# 914-STM32.net
KiCad netlist of a schematic drawn in EAGLE
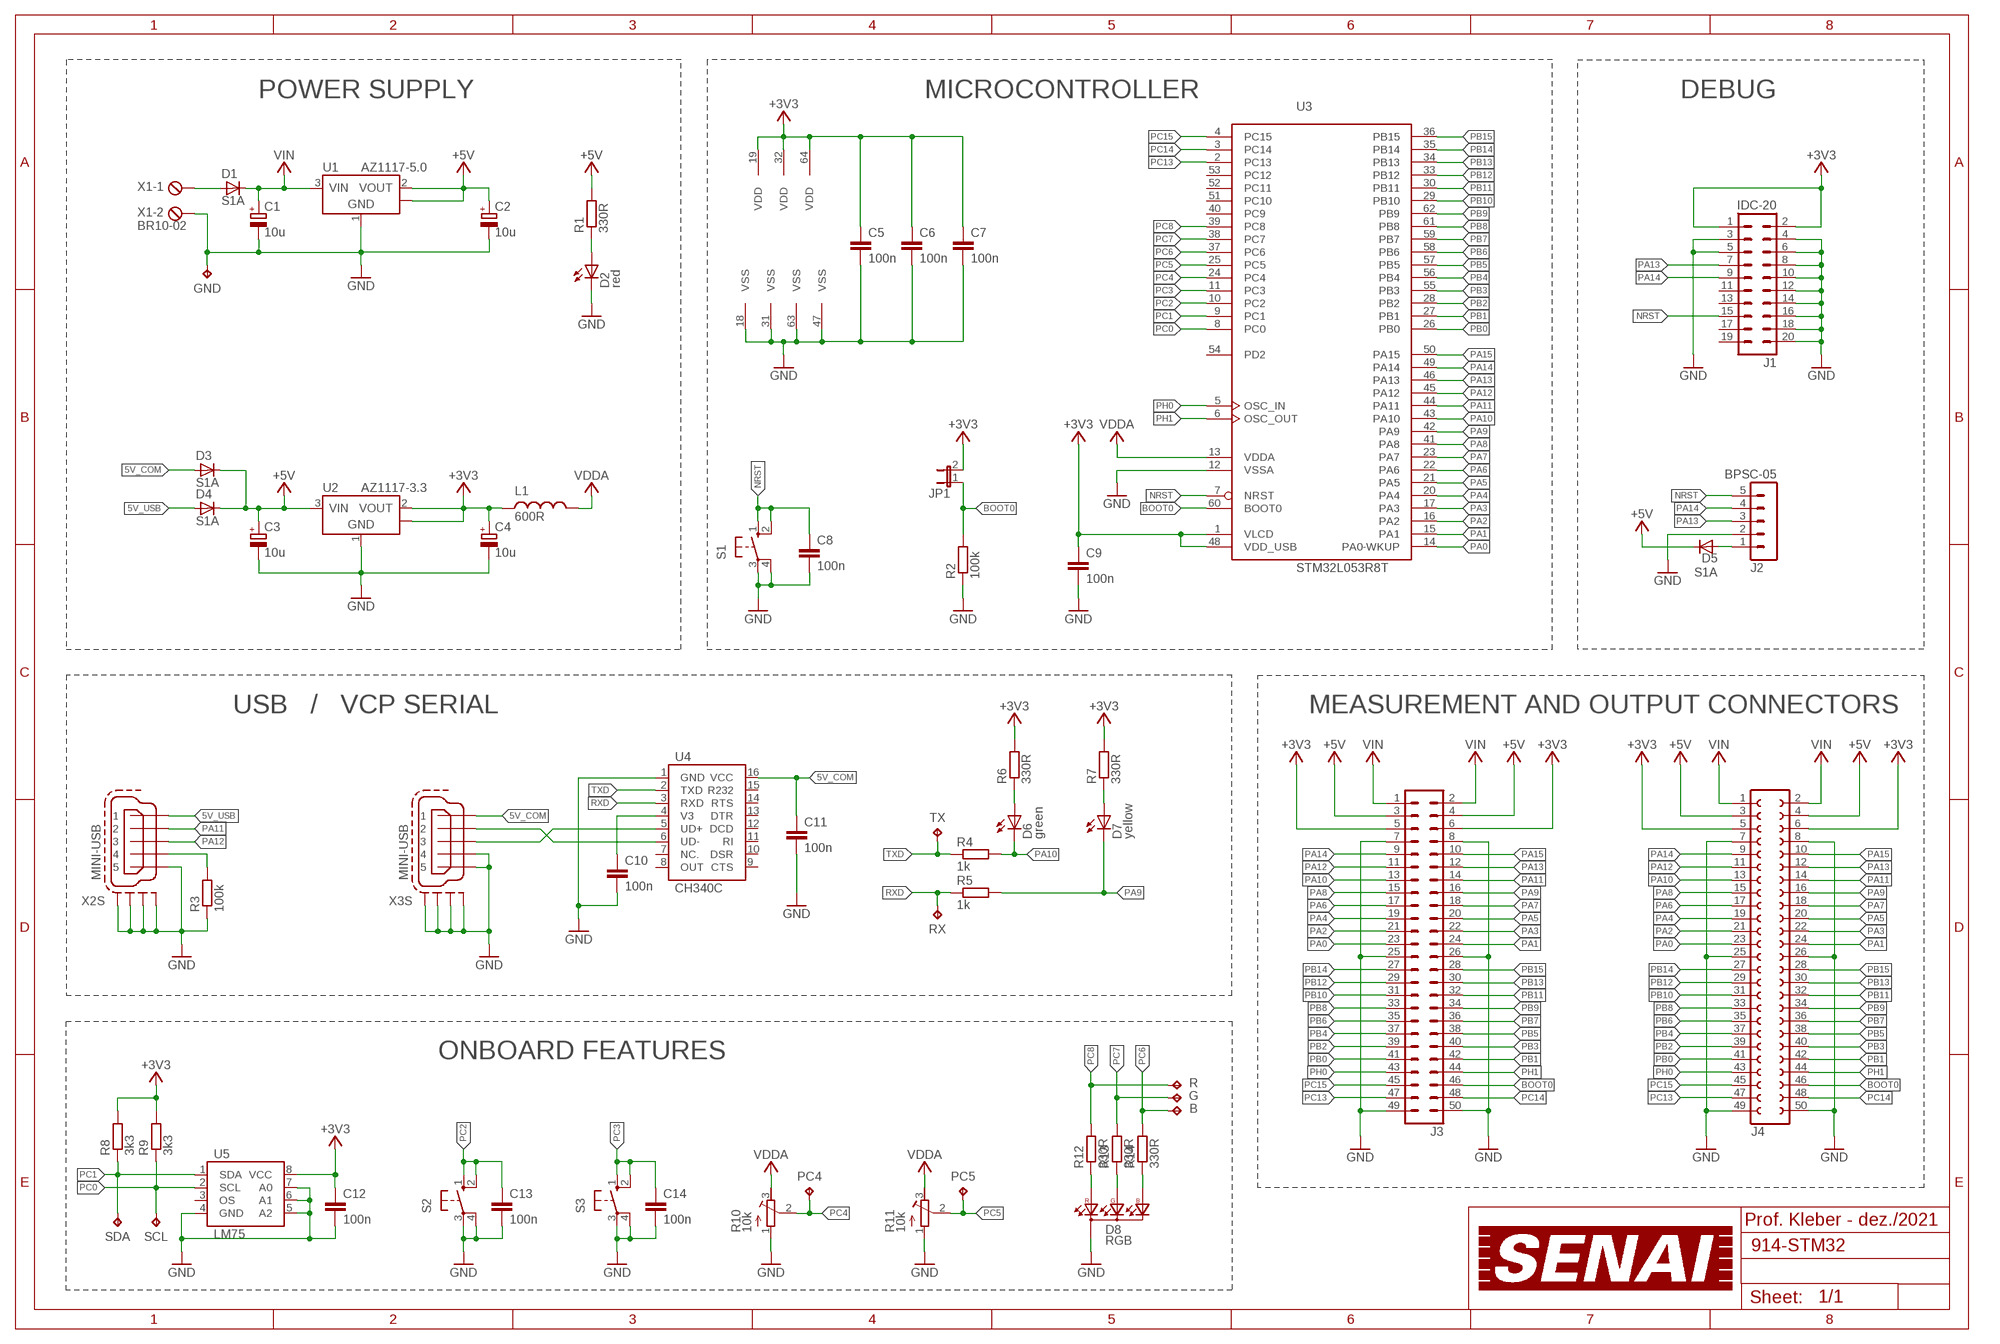
[diagram p0: schematic, sheet 1]

(export (version "E")
  (design (tool "Eeschema 10.0.6"))
  (components
    (comp (ref "1") (value "GND") (footprint "eagle-import:TP1") (libsource (lib "eagle-import") (part "TP")))
    (comp (ref "2") (value "SDA") (footprint "eagle-import:TP1") (libsource (lib "eagle-import") (part "TP")))
    (comp (ref "3") (value "RX") (footprint "eagle-import:TP1") (libsource (lib "eagle-import") (part "TP")))
    (comp (ref "C1")
      (value "10u")
      (footprint "eagle-import:CT1206")
      (libsource (lib "eagle-import") (part "CPOL-1206"))
    )
    (comp (ref "C2")
      (value "10u")
      (footprint "eagle-import:CT1206")
      (libsource (lib "eagle-import") (part "CPOL-1206"))
    )
    (comp (ref "C3")
      (value "10u")
      (footprint "eagle-import:CT1206")
      (libsource (lib "eagle-import") (part "CPOL-1206"))
    )
    (comp (ref "C4")
      (value "10u")
      (footprint "eagle-import:CT1206")
      (libsource (lib "eagle-import") (part "CPOL-1206"))
    )
    (comp (ref "C5")
      (value "100n")
      (footprint "eagle-import:C0603")
      (libsource (lib "eagle-import") (part "C-0603"))
    )
    (comp (ref "C6")
      (value "100n")
      (footprint "eagle-import:C0603")
      (libsource (lib "eagle-import") (part "C-0603"))
    )
    (comp (ref "C7")
      (value "100n")
      (footprint "eagle-import:C0603")
      (libsource (lib "eagle-import") (part "C-0603"))
    )
    (comp (ref "C8")
      (value "100n")
      (footprint "eagle-import:C0603")
      (libsource (lib "eagle-import") (part "C-0603"))
    )
    (comp (ref "C9")
      (value "100n")
      (footprint "eagle-import:C0603")
      (libsource (lib "eagle-import") (part "C-0603"))
    )
    (comp (ref "C10")
      (value "100n")
      (footprint "eagle-import:C0603")
      (libsource (lib "eagle-import") (part "C-0603"))
    )
    (comp (ref "C11")
      (value "100n")
      (footprint "eagle-import:C0603")
      (libsource (lib "eagle-import") (part "C-0603"))
    )
    (comp (ref "C12")
      (value "100n")
      (footprint "eagle-import:C0603")
      (libsource (lib "eagle-import") (part "C-0603"))
    )
    (comp (ref "C13")
      (value "100n")
      (footprint "eagle-import:C0603")
      (libsource (lib "eagle-import") (part "C-0603"))
    )
    (comp (ref "C14")
      (value "100n")
      (footprint "eagle-import:C0603")
      (libsource (lib "eagle-import") (part "C-0603"))
    )
    (comp (ref "D1")
      (value "S1A")
      (footprint "eagle-import:DO214AC")
      (libsource (lib "eagle-import") (part "D-SMA"))
    )
    (comp (ref "D2")
      (value "red")
      (footprint "eagle-import:LED-0805")
      (libsource (lib "eagle-import") (part "LED-0805"))
    )
    (comp (ref "D3")
      (value "S1A")
      (footprint "eagle-import:DO214AC")
      (libsource (lib "eagle-import") (part "D-SMA"))
    )
    (comp (ref "D4")
      (value "S1A")
      (footprint "eagle-import:DO214AC")
      (libsource (lib "eagle-import") (part "D-SMA"))
    )
    (comp (ref "D5")
      (value "S1A")
      (footprint "eagle-import:DO214AC")
      (libsource (lib "eagle-import") (part "D-SMA"))
    )
    (comp (ref "D6")
      (value "green")
      (footprint "eagle-import:LED-0805")
      (libsource (lib "eagle-import") (part "LED-0805"))
    )
    (comp (ref "D7")
      (value "yellow")
      (footprint "eagle-import:LED-0805")
      (libsource (lib "eagle-import") (part "LED-0805"))
    )
    (comp (ref "D8")
      (value "RGB")
      (footprint "eagle-import:LED-RGB-5MM")
      (libsource (lib "eagle-import") (part "LED-RGB-CC"))
    )
    (comp (ref "J1")
      (value "IDC-20")
      (footprint "eagle-import:ML20")
      (libsource (lib "eagle-import") (part "ML20"))
    )
    (comp (ref "J2")
      (value "BPSC-05")
      (footprint "eagle-import:BPSC-05")
      (libsource (lib "eagle-import") (part "CON-?05BPSC-"))
    )
    (comp (ref "J3")
      (value "MA25-2")
      (footprint "eagle-import:MA25-2")
      (libsource (lib "eagle-import") (part "MA25-2"))
    )
    (comp (ref "J4")
      (value "FE25-2")
      (footprint "eagle-import:FE25-2")
      (libsource (lib "eagle-import") (part "FE25-2"))
    )
    (comp (ref "JP1")
      (value "JP1E")
      (footprint "eagle-import:JP1")
      (libsource (lib "eagle-import") (part "JP1E"))
    )
    (comp (ref "L1")
      (value "600R")
      (footprint "eagle-import:L0603")
      (libsource (lib "eagle-import") (part "L-0603"))
    )
    (comp (ref "R1")
      (value "330R")
      (footprint "eagle-import:R0603")
      (libsource (lib "eagle-import") (part "R-0603"))
    )
    (comp (ref "R2")
      (value "100k")
      (footprint "eagle-import:R0603")
      (libsource (lib "eagle-import") (part "R-0603"))
    )
    (comp (ref "R3")
      (value "100k")
      (footprint "eagle-import:R0603")
      (libsource (lib "eagle-import") (part "R-0603"))
    )
    (comp (ref "R4")
      (value "1k")
      (footprint "eagle-import:R0603")
      (libsource (lib "eagle-import") (part "R-0603"))
    )
    (comp (ref "R5")
      (value "1k")
      (footprint "eagle-import:R0603")
      (libsource (lib "eagle-import") (part "R-0603"))
    )
    (comp (ref "R6")
      (value "330R")
      (footprint "eagle-import:R0603")
      (libsource (lib "eagle-import") (part "R-0603"))
    )
    (comp (ref "R7")
      (value "330R")
      (footprint "eagle-import:R0603")
      (libsource (lib "eagle-import") (part "R-0603"))
    )
    (comp (ref "R8")
      (value "3k3")
      (footprint "eagle-import:R0603")
      (libsource (lib "eagle-import") (part "R-0603"))
    )
    (comp (ref "R9")
      (value "3k3")
      (footprint "eagle-import:R0603")
      (libsource (lib "eagle-import") (part "R-0603"))
    )
    (comp (ref "R10")
      (value "10k")
      (footprint "eagle-import:RTRIM3386F")
      (libsource (lib "eagle-import") (part "R-TRIMM3386F"))
    )
    (comp (ref "R11")
      (value "10k")
      (footprint "eagle-import:RTRIM3386F")
      (libsource (lib "eagle-import") (part "R-TRIMM3386F"))
    )
    (comp (ref "R12")
      (value "330R")
      (footprint "eagle-import:R0603")
      (libsource (lib "eagle-import") (part "R-0603"))
    )
    (comp (ref "R13")
      (value "330R")
      (footprint "eagle-import:R0603")
      (libsource (lib "eagle-import") (part "R-0603"))
    )
    (comp (ref "R14")
      (value "330R")
      (footprint "eagle-import:R0603")
      (libsource (lib "eagle-import") (part "R-0603"))
    )
    (comp (ref "S1")
      (value "10-XX")
      (footprint "eagle-import:B3F-10XX")
      (fields (field (name "MPN") "B3F-1000"))
      (libsource (lib "eagle-import") (part "10-XX"))
    )
    (comp (ref "S2")
      (value "10-XX")
      (footprint "eagle-import:B3F-10XX")
      (fields (field (name "MPN") "B3F-1000"))
      (libsource (lib "eagle-import") (part "10-XX"))
    )
    (comp (ref "S3")
      (value "10-XX")
      (footprint "eagle-import:B3F-10XX")
      (fields (field (name "MPN") "B3F-1000"))
      (libsource (lib "eagle-import") (part "10-XX"))
    )
    (comp (ref "TP1") (value "R") (footprint "eagle-import:TP1") (libsource (lib "eagle-import") (part "TP")))
    (comp (ref "TP2") (value "G") (footprint "eagle-import:TP1") (libsource (lib "eagle-import") (part "TP")))
    (comp (ref "TP3")
      (value "SCL")
      (footprint "eagle-import:TP1")
      (libsource (lib "eagle-import") (part "TP"))
    )
    (comp (ref "TP4")
      (value "PC4")
      (footprint "eagle-import:TP1")
      (libsource (lib "eagle-import") (part "TP"))
    )
    (comp (ref "TP5")
      (value "PC5")
      (footprint "eagle-import:TP1")
      (libsource (lib "eagle-import") (part "TP"))
    )
    (comp (ref "TP6") (value "B") (footprint "eagle-import:TP1") (libsource (lib "eagle-import") (part "TP")))
    (comp (ref "TP7")
      (value "TX")
      (footprint "eagle-import:TP1")
      (libsource (lib "eagle-import") (part "TP"))
    )
    (comp (ref "U1")
      (value "AZ1117-5.0")
      (footprint "eagle-import:SOT223")
      (libsource (lib "eagle-import") (part "V-REG"))
    )
    (comp (ref "U2")
      (value "AZ1117-3.3")
      (footprint "eagle-import:SOT223")
      (libsource (lib "eagle-import") (part "V-REG"))
    )
    (comp (ref "U3")
      (value "STM32L053R8T")
      (footprint "eagle-import:LQFP64")
      (libsource (lib "eagle-import") (part "STM32L053RT8"))
    )
    (comp (ref "U4")
      (value "CH340C")
      (footprint "eagle-import:SOIC16")
      (libsource (lib "eagle-import") (part "CH340C"))
    )
    (comp (ref "U5")
      (value "LM75")
      (footprint "eagle-import:SOIC8")
      (libsource (lib "eagle-import") (part "LM75"))
    )
    (comp (ref "X1")
      (value "BR10-02")
      (footprint "eagle-import:BR10-02")
      (libsource (lib "eagle-import") (part "BR10-02"))
    )
    (comp (ref "X2")
      (value "MINI-USB")
      (footprint "eagle-import:32005-201")
      (libsource (lib "eagle-import") (part "MINI-USB-SCHIELD-32005-201"))
    )
    (comp (ref "X3")
      (value "MINI-USB")
      (footprint "eagle-import:32005-201")
      (libsource (lib "eagle-import") (part "MINI-USB-SCHIELD-32005-201"))
    )
  )
  (nets
    (net (code "1") (name "+3V3") (class "Default")
      (node (ref "C12") (pin "1") (pinfunction "1_1") (pintype "passive"))
      (node (ref "C4") (pin "+") (pinfunction "+_+") (pintype "passive"))
      (node (ref "C5") (pin "1") (pinfunction "1_1") (pintype "passive"))
      (node (ref "C6") (pin "1") (pinfunction "1_1") (pintype "passive"))
      (node (ref "C7") (pin "1") (pinfunction "1_1") (pintype "passive"))
      (node (ref "C9") (pin "1") (pinfunction "1_1") (pintype "passive"))
      (node (ref "J1") (pin "1") (pinfunction "1_1") (pintype "passive"))
      (node (ref "J1") (pin "2") (pinfunction "2_2") (pintype "passive"))
      (node (ref "J3") (pin "5") (pinfunction "5_5") (pintype "passive"))
      (node (ref "J3") (pin "6") (pinfunction "6_6") (pintype "passive"))
      (node (ref "J4") (pin "5") (pinfunction "5_5") (pintype "passive"))
      (node (ref "J4") (pin "6") (pinfunction "6_6") (pintype "passive"))
      (node (ref "JP1") (pin "2") (pinfunction "2_2") (pintype "passive"))
      (node (ref "L1") (pin "2") (pinfunction "2_2") (pintype "passive"))
      (node (ref "R6") (pin "2") (pinfunction "2_2") (pintype "passive"))
      (node (ref "R7") (pin "2") (pinfunction "2_2") (pintype "passive"))
      (node (ref "R8") (pin "2") (pinfunction "2_2") (pintype "passive"))
      (node (ref "R9") (pin "2") (pinfunction "2_2") (pintype "passive"))
      (node (ref "U2") (pin "2") (pinfunction "VOUT_2") (pintype "output"))
      (node (ref "U2") (pin "4") (pinfunction "TAB_4") (pintype "output"))
      (node (ref "U3") (pin "1") (pinfunction "VLCD_1") (pintype "power_in"))
      (node (ref "U3") (pin "19") (pinfunction "VDD_19") (pintype "power_in"))
      (node (ref "U3") (pin "32") (pinfunction "VDD_32") (pintype "power_in"))
      (node (ref "U3") (pin "48") (pinfunction "VDD_USB_48") (pintype "power_in"))
      (node (ref "U3") (pin "64") (pinfunction "VDD_64") (pintype "power_in"))
      (node (ref "U5") (pin "8") (pinfunction "VCC_8") (pintype "bidirectional"))
    )
    (net (code "2") (name "+5V") (class "Default")
      (node (ref "C2") (pin "+") (pinfunction "+_+") (pintype "passive"))
      (node (ref "C3") (pin "+") (pinfunction "+_+") (pintype "passive"))
      (node (ref "D3") (pin "C") (pinfunction "C_C") (pintype "passive"))
      (node (ref "D4") (pin "C") (pinfunction "C_C") (pintype "passive"))
      (node (ref "D5") (pin "C") (pinfunction "C_C") (pintype "passive"))
      (node (ref "J3") (pin "3") (pinfunction "3_3") (pintype "passive"))
      (node (ref "J3") (pin "4") (pinfunction "4_4") (pintype "passive"))
      (node (ref "J4") (pin "3") (pinfunction "3_3") (pintype "passive"))
      (node (ref "J4") (pin "4") (pinfunction "4_4") (pintype "passive"))
      (node (ref "R1") (pin "2") (pinfunction "2_2") (pintype "passive"))
      (node (ref "U1") (pin "2") (pinfunction "VOUT_2") (pintype "output"))
      (node (ref "U1") (pin "4") (pinfunction "TAB_4") (pintype "output"))
      (node (ref "U2") (pin "3") (pinfunction "VIN_3") (pintype "input"))
    )
    (net (code "3") (name "5V_COM") (class "Default")
      (node (ref "C11") (pin "1") (pinfunction "1_1") (pintype "passive"))
      (node (ref "D3") (pin "A") (pinfunction "A_A") (pintype "passive"))
      (node (ref "U4") (pin "16") (pinfunction "VCC_16") (pintype "bidirectional"))
      (node (ref "X3") (pin "1") (pinfunction "1_1") (pintype "passive"))
    )
    (net (code "4") (name "5V_USB") (class "Default")
      (node (ref "D4") (pin "A") (pinfunction "A_A") (pintype "passive"))
      (node (ref "X2") (pin "1") (pinfunction "1_1") (pintype "passive"))
    )
    (net (code "5") (name "BOOT0") (class "Default")
      (node (ref "J3") (pin "46") (pinfunction "46_46") (pintype "passive"))
      (node (ref "J4") (pin "46") (pinfunction "46_46") (pintype "passive"))
      (node (ref "JP1") (pin "1") (pinfunction "1_1") (pintype "passive"))
      (node (ref "R2") (pin "2") (pinfunction "2_2") (pintype "passive"))
      (node (ref "U3") (pin "60") (pinfunction "BOOT0_60") (pintype "input"))
    )
    (net (code "6") (name "GND") (class "Default")
      (node (ref "1") (pin "TP") (pinfunction "TP_TP") (pintype "input"))
      (node (ref "C1") (pin "-") (pinfunction "-_-") (pintype "passive"))
      (node (ref "C10") (pin "2") (pinfunction "2_2") (pintype "passive"))
      (node (ref "C11") (pin "2") (pinfunction "2_2") (pintype "passive"))
      (node (ref "C12") (pin "2") (pinfunction "2_2") (pintype "passive"))
      (node (ref "C13") (pin "2") (pinfunction "2_2") (pintype "passive"))
      (node (ref "C14") (pin "2") (pinfunction "2_2") (pintype "passive"))
      (node (ref "C2") (pin "-") (pinfunction "-_-") (pintype "passive"))
      (node (ref "C3") (pin "-") (pinfunction "-_-") (pintype "passive"))
      (node (ref "C4") (pin "-") (pinfunction "-_-") (pintype "passive"))
      (node (ref "C5") (pin "2") (pinfunction "2_2") (pintype "passive"))
      (node (ref "C6") (pin "2") (pinfunction "2_2") (pintype "passive"))
      (node (ref "C7") (pin "2") (pinfunction "2_2") (pintype "passive"))
      (node (ref "C8") (pin "2") (pinfunction "2_2") (pintype "passive"))
      (node (ref "C9") (pin "2") (pinfunction "2_2") (pintype "passive"))
      (node (ref "D2") (pin "C") (pinfunction "C_C") (pintype "passive"))
      (node (ref "D8") (pin "2") (pinfunction "C2_2") (pintype "passive"))
      (node (ref "J1") (pin "10") (pinfunction "10_10") (pintype "passive"))
      (node (ref "J1") (pin "12") (pinfunction "12_12") (pintype "passive"))
      (node (ref "J1") (pin "14") (pinfunction "14_14") (pintype "passive"))
      (node (ref "J1") (pin "16") (pinfunction "16_16") (pintype "passive"))
      (node (ref "J1") (pin "18") (pinfunction "18_18") (pintype "passive"))
      (node (ref "J1") (pin "20") (pinfunction "20_20") (pintype "passive"))
      (node (ref "J1") (pin "3") (pinfunction "3_3") (pintype "passive"))
      (node (ref "J1") (pin "4") (pinfunction "4_4") (pintype "passive"))
      (node (ref "J1") (pin "5") (pinfunction "5_5") (pintype "passive"))
      (node (ref "J1") (pin "6") (pinfunction "6_6") (pintype "passive"))
      (node (ref "J1") (pin "8") (pinfunction "8_8") (pintype "passive"))
      (node (ref "J2") (pin "2") (pinfunction "2_2") (pintype "passive"))
      (node (ref "J3") (pin "25") (pinfunction "25_25") (pintype "passive"))
      (node (ref "J3") (pin "26") (pinfunction "26_26") (pintype "passive"))
      (node (ref "J3") (pin "49") (pinfunction "49_49") (pintype "passive"))
      (node (ref "J3") (pin "50") (pinfunction "50_50") (pintype "passive"))
      (node (ref "J3") (pin "7") (pinfunction "7_7") (pintype "passive"))
      (node (ref "J3") (pin "8") (pinfunction "8_8") (pintype "passive"))
      (node (ref "J4") (pin "25") (pinfunction "25_25") (pintype "passive"))
      (node (ref "J4") (pin "26") (pinfunction "26_26") (pintype "passive"))
      (node (ref "J4") (pin "49") (pinfunction "49_49") (pintype "passive"))
      (node (ref "J4") (pin "50") (pinfunction "50_50") (pintype "passive"))
      (node (ref "J4") (pin "7") (pinfunction "7_7") (pintype "passive"))
      (node (ref "J4") (pin "8") (pinfunction "8_8") (pintype "passive"))
      (node (ref "R10") (pin "1") (pinfunction "A_1") (pintype "passive"))
      (node (ref "R11") (pin "1") (pinfunction "A_1") (pintype "passive"))
      (node (ref "R2") (pin "1") (pinfunction "1_1") (pintype "passive"))
      (node (ref "R3") (pin "1") (pinfunction "1_1") (pintype "passive"))
      (node (ref "S1") (pin "3") (pinfunction "P_3") (pintype "passive"))
      (node (ref "S1") (pin "4") (pinfunction "P1_4") (pintype "passive"))
      (node (ref "S2") (pin "3") (pinfunction "P_3") (pintype "passive"))
      (node (ref "S2") (pin "4") (pinfunction "P1_4") (pintype "passive"))
      (node (ref "S3") (pin "3") (pinfunction "P_3") (pintype "passive"))
      (node (ref "S3") (pin "4") (pinfunction "P1_4") (pintype "passive"))
      (node (ref "U1") (pin "1") (pinfunction "GND_1") (pintype "power_in"))
      (node (ref "U2") (pin "1") (pinfunction "GND_1") (pintype "power_in"))
      (node (ref "U3") (pin "12") (pinfunction "VSSA_12") (pintype "power_in"))
      (node (ref "U3") (pin "18") (pinfunction "VSS_18") (pintype "power_in"))
      (node (ref "U3") (pin "31") (pinfunction "VSS_31") (pintype "power_in"))
      (node (ref "U3") (pin "47") (pinfunction "VSS_47") (pintype "power_in"))
      (node (ref "U3") (pin "63") (pinfunction "VSS_63") (pintype "power_in"))
      (node (ref "U4") (pin "1") (pinfunction "GND_1") (pintype "bidirectional"))
      (node (ref "U5") (pin "4") (pinfunction "GND_4") (pintype "bidirectional"))
      (node (ref "U5") (pin "5") (pinfunction "A2_5") (pintype "bidirectional"))
      (node (ref "U5") (pin "6") (pinfunction "A1_6") (pintype "bidirectional"))
      (node (ref "U5") (pin "7") (pinfunction "A0_7") (pintype "bidirectional"))
      (node (ref "X1") (pin "2") (pinfunction "1_2") (pintype "passive"))
      (node (ref "X2") (pin "5") (pinfunction "5_5") (pintype "passive"))
      (node (ref "X2") (pin "M1") (pinfunction "S1_M1") (pintype "passive"))
      (node (ref "X2") (pin "M2") (pinfunction "S2_M2") (pintype "passive"))
      (node (ref "X2") (pin "M3") (pinfunction "S3_M3") (pintype "passive"))
      (node (ref "X2") (pin "M4") (pinfunction "S4_M4") (pintype "passive"))
      (node (ref "X3") (pin "4") (pinfunction "4_4") (pintype "passive"))
      (node (ref "X3") (pin "5") (pinfunction "5_5") (pintype "passive"))
      (node (ref "X3") (pin "M1") (pinfunction "S1_M1") (pintype "passive"))
      (node (ref "X3") (pin "M2") (pinfunction "S2_M2") (pintype "passive"))
      (node (ref "X3") (pin "M3") (pinfunction "S3_M3") (pintype "passive"))
      (node (ref "X3") (pin "M4") (pinfunction "S4_M4") (pintype "passive"))
    )
    (net (code "7") (name "NRST") (class "Default")
      (node (ref "C8") (pin "1") (pinfunction "1_1") (pintype "passive"))
      (node (ref "J1") (pin "15") (pinfunction "15_15") (pintype "passive"))
      (node (ref "J2") (pin "5") (pinfunction "5_5") (pintype "passive"))
      (node (ref "S1") (pin "1") (pinfunction "S_1") (pintype "passive"))
      (node (ref "S1") (pin "2") (pinfunction "S1_2") (pintype "passive"))
      (node (ref "U3") (pin "7") (pinfunction "NRST_7") (pintype "bidirectional"))
    )
    (net (code "8") (name "Net-(D1-PadA)") (class "Default")
      (node (ref "D1") (pin "A") (pinfunction "A_A") (pintype "passive"))
      (node (ref "X1") (pin "1") (pinfunction "1_1") (pintype "passive"))
    )
    (net (code "9") (name "Net-(D2-PadA)") (class "Default")
      (node (ref "D2") (pin "A") (pinfunction "A_A") (pintype "passive"))
      (node (ref "R1") (pin "1") (pinfunction "1_1") (pintype "passive"))
    )
    (net (code "10") (name "Net-(D5-PadA)") (class "Default")
      (node (ref "D5") (pin "A") (pinfunction "A_A") (pintype "passive"))
      (node (ref "J2") (pin "1") (pinfunction "1_1") (pintype "passive"))
    )
    (net (code "11") (name "Net-(D6-PadA)") (class "Default")
      (node (ref "D6") (pin "A") (pinfunction "A_A") (pintype "passive"))
      (node (ref "R6") (pin "1") (pinfunction "1_1") (pintype "passive"))
    )
    (net (code "12") (name "Net-(D7-PadA)") (class "Default")
      (node (ref "D7") (pin "A") (pinfunction "A_A") (pintype "passive"))
      (node (ref "R7") (pin "1") (pinfunction "1_1") (pintype "passive"))
    )
    (net (code "13") (name "Net-(D8-ABLUE)") (class "Default")
      (node (ref "D8") (pin "4") (pinfunction "ABLUE_4") (pintype "passive"))
      (node (ref "R14") (pin "1") (pinfunction "1_1") (pintype "passive"))
    )
    (net (code "14") (name "Net-(D8-AGREEN)") (class "Default")
      (node (ref "D8") (pin "3") (pinfunction "AGREEN_3") (pintype "passive"))
      (node (ref "R13") (pin "1") (pinfunction "1_1") (pintype "passive"))
    )
    (net (code "15") (name "Net-(D8-ARED)") (class "Default")
      (node (ref "D8") (pin "1") (pinfunction "ARED_1") (pintype "passive"))
      (node (ref "R12") (pin "1") (pinfunction "1_1") (pintype "passive"))
    )
    (net (code "16") (name "Net-(R3-Pad2)") (class "Default")
      (node (ref "R3") (pin "2") (pinfunction "2_2") (pintype "passive"))
      (node (ref "X2") (pin "4") (pinfunction "4_4") (pintype "passive"))
    )
    (net (code "17") (name "Net-(U4-UD+)") (class "Default")
      (node (ref "U4") (pin "5") (pinfunction "UD+_5") (pintype "bidirectional"))
      (node (ref "X3") (pin "3") (pinfunction "3_3") (pintype "passive"))
    )
    (net (code "18") (name "Net-(U4-UD-)") (class "Default")
      (node (ref "U4") (pin "6") (pinfunction "UD-_6") (pintype "bidirectional"))
      (node (ref "X3") (pin "2") (pinfunction "2_2") (pintype "passive"))
    )
    (net (code "19") (name "Net-(U4-V3)") (class "Default")
      (node (ref "C10") (pin "1") (pinfunction "1_1") (pintype "passive"))
      (node (ref "U4") (pin "4") (pinfunction "V3_4") (pintype "bidirectional"))
    )
    (net (code "20") (name "PA0") (class "Default")
      (node (ref "J3") (pin "23") (pinfunction "23_23") (pintype "passive"))
      (node (ref "J4") (pin "23") (pinfunction "23_23") (pintype "passive"))
      (node (ref "U3") (pin "14") (pinfunction "PA0-WKUP_14") (pintype "bidirectional"))
    )
    (net (code "21") (name "PA1") (class "Default")
      (node (ref "J3") (pin "24") (pinfunction "24_24") (pintype "passive"))
      (node (ref "J4") (pin "24") (pinfunction "24_24") (pintype "passive"))
      (node (ref "U3") (pin "15") (pinfunction "PA1_15") (pintype "bidirectional"))
    )
    (net (code "22") (name "PA2") (class "Default")
      (node (ref "J3") (pin "21") (pinfunction "21_21") (pintype "passive"))
      (node (ref "J4") (pin "21") (pinfunction "21_21") (pintype "passive"))
      (node (ref "U3") (pin "16") (pinfunction "PA2_16") (pintype "bidirectional"))
    )
    (net (code "23") (name "PA3") (class "Default")
      (node (ref "J3") (pin "22") (pinfunction "22_22") (pintype "passive"))
      (node (ref "J4") (pin "22") (pinfunction "22_22") (pintype "passive"))
      (node (ref "U3") (pin "17") (pinfunction "PA3_17") (pintype "bidirectional"))
    )
    (net (code "24") (name "PA4") (class "Default")
      (node (ref "J3") (pin "19") (pinfunction "19_19") (pintype "passive"))
      (node (ref "J4") (pin "19") (pinfunction "19_19") (pintype "passive"))
      (node (ref "U3") (pin "20") (pinfunction "PA4_20") (pintype "bidirectional"))
    )
    (net (code "25") (name "PA5") (class "Default")
      (node (ref "J3") (pin "20") (pinfunction "20_20") (pintype "passive"))
      (node (ref "J4") (pin "20") (pinfunction "20_20") (pintype "passive"))
      (node (ref "U3") (pin "21") (pinfunction "PA5_21") (pintype "bidirectional"))
    )
    (net (code "26") (name "PA6") (class "Default")
      (node (ref "J3") (pin "17") (pinfunction "17_17") (pintype "passive"))
      (node (ref "J4") (pin "17") (pinfunction "17_17") (pintype "passive"))
      (node (ref "U3") (pin "22") (pinfunction "PA6_22") (pintype "bidirectional"))
    )
    (net (code "27") (name "PA7") (class "Default")
      (node (ref "J3") (pin "18") (pinfunction "18_18") (pintype "passive"))
      (node (ref "J4") (pin "18") (pinfunction "18_18") (pintype "passive"))
      (node (ref "U3") (pin "23") (pinfunction "PA7_23") (pintype "bidirectional"))
    )
    (net (code "28") (name "PA8") (class "Default")
      (node (ref "J3") (pin "15") (pinfunction "15_15") (pintype "passive"))
      (node (ref "J4") (pin "15") (pinfunction "15_15") (pintype "passive"))
      (node (ref "U3") (pin "41") (pinfunction "PA8_41") (pintype "bidirectional"))
    )
    (net (code "29") (name "PA9") (class "Default")
      (node (ref "D7") (pin "C") (pinfunction "C_C") (pintype "passive"))
      (node (ref "J3") (pin "16") (pinfunction "16_16") (pintype "passive"))
      (node (ref "J4") (pin "16") (pinfunction "16_16") (pintype "passive"))
      (node (ref "R5") (pin "2") (pinfunction "2_2") (pintype "passive"))
      (node (ref "U3") (pin "42") (pinfunction "PA9_42") (pintype "bidirectional"))
    )
    (net (code "30") (name "PA10") (class "Default")
      (node (ref "D6") (pin "C") (pinfunction "C_C") (pintype "passive"))
      (node (ref "J3") (pin "13") (pinfunction "13_13") (pintype "passive"))
      (node (ref "J4") (pin "13") (pinfunction "13_13") (pintype "passive"))
      (node (ref "R4") (pin "2") (pinfunction "2_2") (pintype "passive"))
      (node (ref "U3") (pin "43") (pinfunction "PA10_43") (pintype "bidirectional"))
    )
    (net (code "31") (name "PA11") (class "Default")
      (node (ref "J3") (pin "14") (pinfunction "14_14") (pintype "passive"))
      (node (ref "J4") (pin "14") (pinfunction "14_14") (pintype "passive"))
      (node (ref "U3") (pin "44") (pinfunction "PA11_44") (pintype "bidirectional"))
      (node (ref "X2") (pin "2") (pinfunction "2_2") (pintype "passive"))
    )
    (net (code "32") (name "PA12") (class "Default")
      (node (ref "J3") (pin "11") (pinfunction "11_11") (pintype "passive"))
      (node (ref "J4") (pin "11") (pinfunction "11_11") (pintype "passive"))
      (node (ref "U3") (pin "45") (pinfunction "PA12_45") (pintype "bidirectional"))
      (node (ref "X2") (pin "3") (pinfunction "3_3") (pintype "passive"))
    )
    (net (code "33") (name "PA13") (class "Default")
      (node (ref "J1") (pin "7") (pinfunction "7_7") (pintype "passive"))
      (node (ref "J2") (pin "3") (pinfunction "3_3") (pintype "passive"))
      (node (ref "J3") (pin "12") (pinfunction "12_12") (pintype "passive"))
      (node (ref "J4") (pin "12") (pinfunction "12_12") (pintype "passive"))
      (node (ref "U3") (pin "46") (pinfunction "PA13_46") (pintype "bidirectional"))
    )
    (net (code "34") (name "PA14") (class "Default")
      (node (ref "J1") (pin "9") (pinfunction "9_9") (pintype "passive"))
      (node (ref "J2") (pin "4") (pinfunction "4_4") (pintype "passive"))
      (node (ref "J3") (pin "9") (pinfunction "9_9") (pintype "passive"))
      (node (ref "J4") (pin "9") (pinfunction "9_9") (pintype "passive"))
      (node (ref "U3") (pin "49") (pinfunction "PA14_49") (pintype "bidirectional"))
    )
    (net (code "35") (name "PA15") (class "Default")
      (node (ref "J3") (pin "10") (pinfunction "10_10") (pintype "passive"))
      (node (ref "J4") (pin "10") (pinfunction "10_10") (pintype "passive"))
      (node (ref "U3") (pin "50") (pinfunction "PA15_50") (pintype "bidirectional"))
    )
    (net (code "36") (name "PB0") (class "Default")
      (node (ref "J3") (pin "41") (pinfunction "41_41") (pintype "passive"))
      (node (ref "J4") (pin "41") (pinfunction "41_41") (pintype "passive"))
      (node (ref "U3") (pin "26") (pinfunction "PB0_26") (pintype "bidirectional"))
    )
    (net (code "37") (name "PB1") (class "Default")
      (node (ref "J3") (pin "42") (pinfunction "42_42") (pintype "passive"))
      (node (ref "J4") (pin "42") (pinfunction "42_42") (pintype "passive"))
      (node (ref "U3") (pin "27") (pinfunction "PB1_27") (pintype "bidirectional"))
    )
    (net (code "38") (name "PB2") (class "Default")
      (node (ref "J3") (pin "39") (pinfunction "39_39") (pintype "passive"))
      (node (ref "J4") (pin "39") (pinfunction "39_39") (pintype "passive"))
      (node (ref "U3") (pin "28") (pinfunction "PB2_28") (pintype "bidirectional"))
    )
    (net (code "39") (name "PB3") (class "Default")
      (node (ref "J3") (pin "40") (pinfunction "40_40") (pintype "passive"))
      (node (ref "J4") (pin "40") (pinfunction "40_40") (pintype "passive"))
      (node (ref "U3") (pin "55") (pinfunction "PB3_55") (pintype "bidirectional"))
    )
    (net (code "40") (name "PB4") (class "Default")
      (node (ref "J3") (pin "37") (pinfunction "37_37") (pintype "passive"))
      (node (ref "J4") (pin "37") (pinfunction "37_37") (pintype "passive"))
      (node (ref "U3") (pin "56") (pinfunction "PB4_56") (pintype "bidirectional"))
    )
    (net (code "41") (name "PB5") (class "Default")
      (node (ref "J3") (pin "38") (pinfunction "38_38") (pintype "passive"))
      (node (ref "J4") (pin "38") (pinfunction "38_38") (pintype "passive"))
      (node (ref "U3") (pin "57") (pinfunction "PB5_57") (pintype "bidirectional"))
    )
    (net (code "42") (name "PB6") (class "Default")
      (node (ref "J3") (pin "35") (pinfunction "35_35") (pintype "passive"))
      (node (ref "J4") (pin "35") (pinfunction "35_35") (pintype "passive"))
      (node (ref "U3") (pin "58") (pinfunction "PB6_58") (pintype "bidirectional"))
    )
    (net (code "43") (name "PB7") (class "Default")
      (node (ref "J3") (pin "36") (pinfunction "36_36") (pintype "passive"))
      (node (ref "J4") (pin "36") (pinfunction "36_36") (pintype "passive"))
      (node (ref "U3") (pin "59") (pinfunction "PB7_59") (pintype "bidirectional"))
    )
    (net (code "44") (name "PB8") (class "Default")
      (node (ref "J3") (pin "33") (pinfunction "33_33") (pintype "passive"))
      (node (ref "J4") (pin "33") (pinfunction "33_33") (pintype "passive"))
      (node (ref "U3") (pin "61") (pinfunction "PB8_61") (pintype "bidirectional"))
    )
    (net (code "45") (name "PB9") (class "Default")
      (node (ref "J3") (pin "34") (pinfunction "34_34") (pintype "passive"))
      (node (ref "J4") (pin "34") (pinfunction "34_34") (pintype "passive"))
      (node (ref "U3") (pin "62") (pinfunction "PB9_62") (pintype "bidirectional"))
    )
    (net (code "46") (name "PB10") (class "Default")
      (node (ref "J3") (pin "31") (pinfunction "31_31") (pintype "passive"))
      (node (ref "J4") (pin "31") (pinfunction "31_31") (pintype "passive"))
      (node (ref "U3") (pin "29") (pinfunction "PB10_29") (pintype "bidirectional"))
    )
    (net (code "47") (name "PB11") (class "Default")
      (node (ref "J3") (pin "32") (pinfunction "32_32") (pintype "passive"))
      (node (ref "J4") (pin "32") (pinfunction "32_32") (pintype "passive"))
      (node (ref "U3") (pin "30") (pinfunction "PB11_30") (pintype "bidirectional"))
    )
    (net (code "48") (name "PB12") (class "Default")
      (node (ref "J3") (pin "29") (pinfunction "29_29") (pintype "passive"))
      (node (ref "J4") (pin "29") (pinfunction "29_29") (pintype "passive"))
      (node (ref "U3") (pin "33") (pinfunction "PB12_33") (pintype "bidirectional"))
    )
    (net (code "49") (name "PB13") (class "Default")
      (node (ref "J3") (pin "30") (pinfunction "30_30") (pintype "passive"))
      (node (ref "J4") (pin "30") (pinfunction "30_30") (pintype "passive"))
      (node (ref "U3") (pin "34") (pinfunction "PB13_34") (pintype "bidirectional"))
    )
    (net (code "50") (name "PB14") (class "Default")
      (node (ref "J3") (pin "27") (pinfunction "27_27") (pintype "passive"))
      (node (ref "J4") (pin "27") (pinfunction "27_27") (pintype "passive"))
      (node (ref "U3") (pin "35") (pinfunction "PB14_35") (pintype "bidirectional"))
    )
    (net (code "51") (name "PB15") (class "Default")
      (node (ref "J3") (pin "28") (pinfunction "28_28") (pintype "passive"))
      (node (ref "J4") (pin "28") (pinfunction "28_28") (pintype "passive"))
      (node (ref "U3") (pin "36") (pinfunction "PB15_36") (pintype "bidirectional"))
    )
    (net (code "52") (name "PC0") (class "Default")
      (node (ref "R9") (pin "1") (pinfunction "1_1") (pintype "passive"))
      (node (ref "TP3") (pin "TP") (pinfunction "TP_TP") (pintype "input"))
      (node (ref "U3") (pin "8") (pinfunction "PC0_8") (pintype "bidirectional"))
      (node (ref "U5") (pin "2") (pinfunction "SCL_2") (pintype "bidirectional"))
    )
    (net (code "53") (name "PC1") (class "Default")
      (node (ref "2") (pin "TP") (pinfunction "TP_TP") (pintype "input"))
      (node (ref "R8") (pin "1") (pinfunction "1_1") (pintype "passive"))
      (node (ref "U3") (pin "9") (pinfunction "PC1_9") (pintype "bidirectional"))
      (node (ref "U5") (pin "1") (pinfunction "SDA_1") (pintype "bidirectional"))
    )
    (net (code "54") (name "PC2") (class "Default")
      (node (ref "C13") (pin "1") (pinfunction "1_1") (pintype "passive"))
      (node (ref "S2") (pin "1") (pinfunction "S_1") (pintype "passive"))
      (node (ref "S2") (pin "2") (pinfunction "S1_2") (pintype "passive"))
      (node (ref "U3") (pin "10") (pinfunction "PC2_10") (pintype "bidirectional"))
    )
    (net (code "55") (name "PC3") (class "Default")
      (node (ref "C14") (pin "1") (pinfunction "1_1") (pintype "passive"))
      (node (ref "S3") (pin "1") (pinfunction "S_1") (pintype "passive"))
      (node (ref "S3") (pin "2") (pinfunction "S1_2") (pintype "passive"))
      (node (ref "U3") (pin "11") (pinfunction "PC3_11") (pintype "bidirectional"))
    )
    (net (code "56") (name "PC4") (class "Default")
      (node (ref "R10") (pin "2") (pinfunction "S_2") (pintype "passive"))
      (node (ref "TP4") (pin "TP") (pinfunction "TP_TP") (pintype "input"))
      (node (ref "U3") (pin "24") (pinfunction "PC4_24") (pintype "bidirectional"))
    )
    (net (code "57") (name "PC5") (class "Default")
      (node (ref "R11") (pin "2") (pinfunction "S_2") (pintype "passive"))
      (node (ref "TP5") (pin "TP") (pinfunction "TP_TP") (pintype "input"))
      (node (ref "U3") (pin "25") (pinfunction "PC5_25") (pintype "bidirectional"))
    )
    (net (code "58") (name "PC6") (class "Default")
      (node (ref "R14") (pin "2") (pinfunction "2_2") (pintype "passive"))
      (node (ref "TP6") (pin "TP") (pinfunction "TP_TP") (pintype "input"))
      (node (ref "U3") (pin "37") (pinfunction "PC6_37") (pintype "bidirectional"))
    )
    (net (code "59") (name "PC7") (class "Default")
      (node (ref "R13") (pin "2") (pinfunction "2_2") (pintype "passive"))
      (node (ref "TP2") (pin "TP") (pinfunction "TP_TP") (pintype "input"))
      (node (ref "U3") (pin "38") (pinfunction "PC7_38") (pintype "bidirectional"))
    )
    (net (code "60") (name "PC8") (class "Default")
      (node (ref "R12") (pin "2") (pinfunction "2_2") (pintype "passive"))
      (node (ref "TP1") (pin "TP") (pinfunction "TP_TP") (pintype "input"))
      (node (ref "U3") (pin "39") (pinfunction "PC8_39") (pintype "bidirectional"))
    )
    (net (code "61") (name "PC13") (class "Default")
      (node (ref "J3") (pin "47") (pinfunction "47_47") (pintype "passive"))
      (node (ref "J4") (pin "47") (pinfunction "47_47") (pintype "passive"))
      (node (ref "U3") (pin "2") (pinfunction "PC13_2") (pintype "bidirectional"))
    )
    (net (code "62") (name "PC14") (class "Default")
      (node (ref "J3") (pin "48") (pinfunction "48_48") (pintype "passive"))
      (node (ref "J4") (pin "48") (pinfunction "48_48") (pintype "passive"))
      (node (ref "U3") (pin "3") (pinfunction "PC14_3") (pintype "bidirectional"))
    )
    (net (code "63") (name "PC15") (class "Default")
      (node (ref "J3") (pin "45") (pinfunction "45_45") (pintype "passive"))
      (node (ref "J4") (pin "45") (pinfunction "45_45") (pintype "passive"))
      (node (ref "U3") (pin "4") (pinfunction "PC15_4") (pintype "bidirectional"))
    )
    (net (code "64") (name "PH0") (class "Default")
      (node (ref "J3") (pin "43") (pinfunction "43_43") (pintype "passive"))
      (node (ref "J4") (pin "43") (pinfunction "43_43") (pintype "passive"))
      (node (ref "U3") (pin "5") (pinfunction "OSC_IN_5") (pintype "bidirectional"))
    )
    (net (code "65") (name "PH1") (class "Default")
      (node (ref "J3") (pin "44") (pinfunction "44_44") (pintype "passive"))
      (node (ref "J4") (pin "44") (pinfunction "44_44") (pintype "passive"))
      (node (ref "U3") (pin "6") (pinfunction "OSC_OUT_6") (pintype "bidirectional"))
    )
    (net (code "66") (name "RXD") (class "Default")
      (node (ref "3") (pin "TP") (pinfunction "TP_TP") (pintype "input"))
      (node (ref "R5") (pin "1") (pinfunction "1_1") (pintype "passive"))
      (node (ref "U4") (pin "3") (pinfunction "RXD_3") (pintype "bidirectional"))
    )
    (net (code "67") (name "TXD") (class "Default")
      (node (ref "R4") (pin "1") (pinfunction "1_1") (pintype "passive"))
      (node (ref "TP7") (pin "TP") (pinfunction "TP_TP") (pintype "input"))
      (node (ref "U4") (pin "2") (pinfunction "TXD_2") (pintype "bidirectional"))
    )
    (net (code "68") (name "VDDA") (class "Default")
      (node (ref "L1") (pin "1") (pinfunction "1_1") (pintype "passive"))
      (node (ref "R10") (pin "3") (pinfunction "E_3") (pintype "passive"))
      (node (ref "R11") (pin "3") (pinfunction "E_3") (pintype "passive"))
      (node (ref "U3") (pin "13") (pinfunction "VDDA_13") (pintype "power_in"))
    )
    (net (code "69") (name "VIN") (class "Default")
      (node (ref "C1") (pin "+") (pinfunction "+_+") (pintype "passive"))
      (node (ref "D1") (pin "C") (pinfunction "C_C") (pintype "passive"))
      (node (ref "J3") (pin "1") (pinfunction "1_1") (pintype "passive"))
      (node (ref "J3") (pin "2") (pinfunction "2_2") (pintype "passive"))
      (node (ref "J4") (pin "1") (pinfunction "1_1") (pintype "passive"))
      (node (ref "J4") (pin "2") (pinfunction "2_2") (pintype "passive"))
      (node (ref "U1") (pin "3") (pinfunction "VIN_3") (pintype "input"))
    )
    (net (code "70") (name "unconnected-(J1-Pad11)") (class "Default")
      (node (ref "J1") (pin "11") (pinfunction "11_11") (pintype "passive"))
    )
    (net (code "71") (name "unconnected-(J1-Pad13)") (class "Default")
      (node (ref "J1") (pin "13") (pinfunction "13_13") (pintype "passive"))
    )
    (net (code "72") (name "unconnected-(J1-Pad17)") (class "Default")
      (node (ref "J1") (pin "17") (pinfunction "17_17") (pintype "passive"))
    )
    (net (code "73") (name "unconnected-(J1-Pad19)") (class "Default")
      (node (ref "J1") (pin "19") (pinfunction "19_19") (pintype "passive"))
    )
    (net (code "74") (name "unconnected-(U3A-PC9-Pad40)") (class "Default")
      (node (ref "U3") (pin "40") (pinfunction "PC9_40") (pintype "bidirectional"))
    )
    (net (code "75") (name "unconnected-(U3A-PC10-Pad51)") (class "Default")
      (node (ref "U3") (pin "51") (pinfunction "PC10_51") (pintype "bidirectional"))
    )
    (net (code "76") (name "unconnected-(U3A-PC11-Pad52)") (class "Default")
      (node (ref "U3") (pin "52") (pinfunction "PC11_52") (pintype "bidirectional"))
    )
    (net (code "77") (name "unconnected-(U3A-PC12-Pad53)") (class "Default")
      (node (ref "U3") (pin "53") (pinfunction "PC12_53") (pintype "bidirectional"))
    )
    (net (code "78") (name "unconnected-(U3A-PD2-Pad54)") (class "Default")
      (node (ref "U3") (pin "54") (pinfunction "PD2_54") (pintype "bidirectional"))
    )
    (net (code "79") (name "unconnected-(U4-CTS-Pad9)") (class "Default")
      (node (ref "U4") (pin "9") (pinfunction "CTS_9") (pintype "bidirectional"))
    )
    (net (code "80") (name "unconnected-(U4-DCD-Pad12)") (class "Default")
      (node (ref "U4") (pin "12") (pinfunction "DCD_12") (pintype "bidirectional"))
    )
    (net (code "81") (name "unconnected-(U4-DSR-Pad10)") (class "Default")
      (node (ref "U4") (pin "10") (pinfunction "DSR_10") (pintype "bidirectional"))
    )
    (net (code "82") (name "unconnected-(U4-DTR-Pad13)") (class "Default")
      (node (ref "U4") (pin "13") (pinfunction "DTR_13") (pintype "bidirectional"))
    )
    (net (code "83") (name "unconnected-(U4-NC.-Pad7)") (class "Default")
      (node (ref "U4") (pin "7") (pinfunction "NC._7") (pintype "bidirectional"))
    )
    (net (code "84") (name "unconnected-(U4-OUT-Pad8)") (class "Default")
      (node (ref "U4") (pin "8") (pinfunction "OUT_8") (pintype "bidirectional"))
    )
    (net (code "85") (name "unconnected-(U4-R232-Pad15)") (class "Default")
      (node (ref "U4") (pin "15") (pinfunction "R232_15") (pintype "bidirectional"))
    )
    (net (code "86") (name "unconnected-(U4-RI-Pad11)") (class "Default")
      (node (ref "U4") (pin "11") (pinfunction "RI_11") (pintype "bidirectional"))
    )
    (net (code "87") (name "unconnected-(U4-RTS-Pad14)") (class "Default")
      (node (ref "U4") (pin "14") (pinfunction "RTS_14") (pintype "bidirectional"))
    )
    (net (code "88") (name "unconnected-(U5-OS-Pad3)") (class "Default")
      (node (ref "U5") (pin "3") (pinfunction "OS_3") (pintype "bidirectional"))
    )
  )
)
